# Basic_Arduino.net
KiCad netlist of a schematic drawn in EAGLE
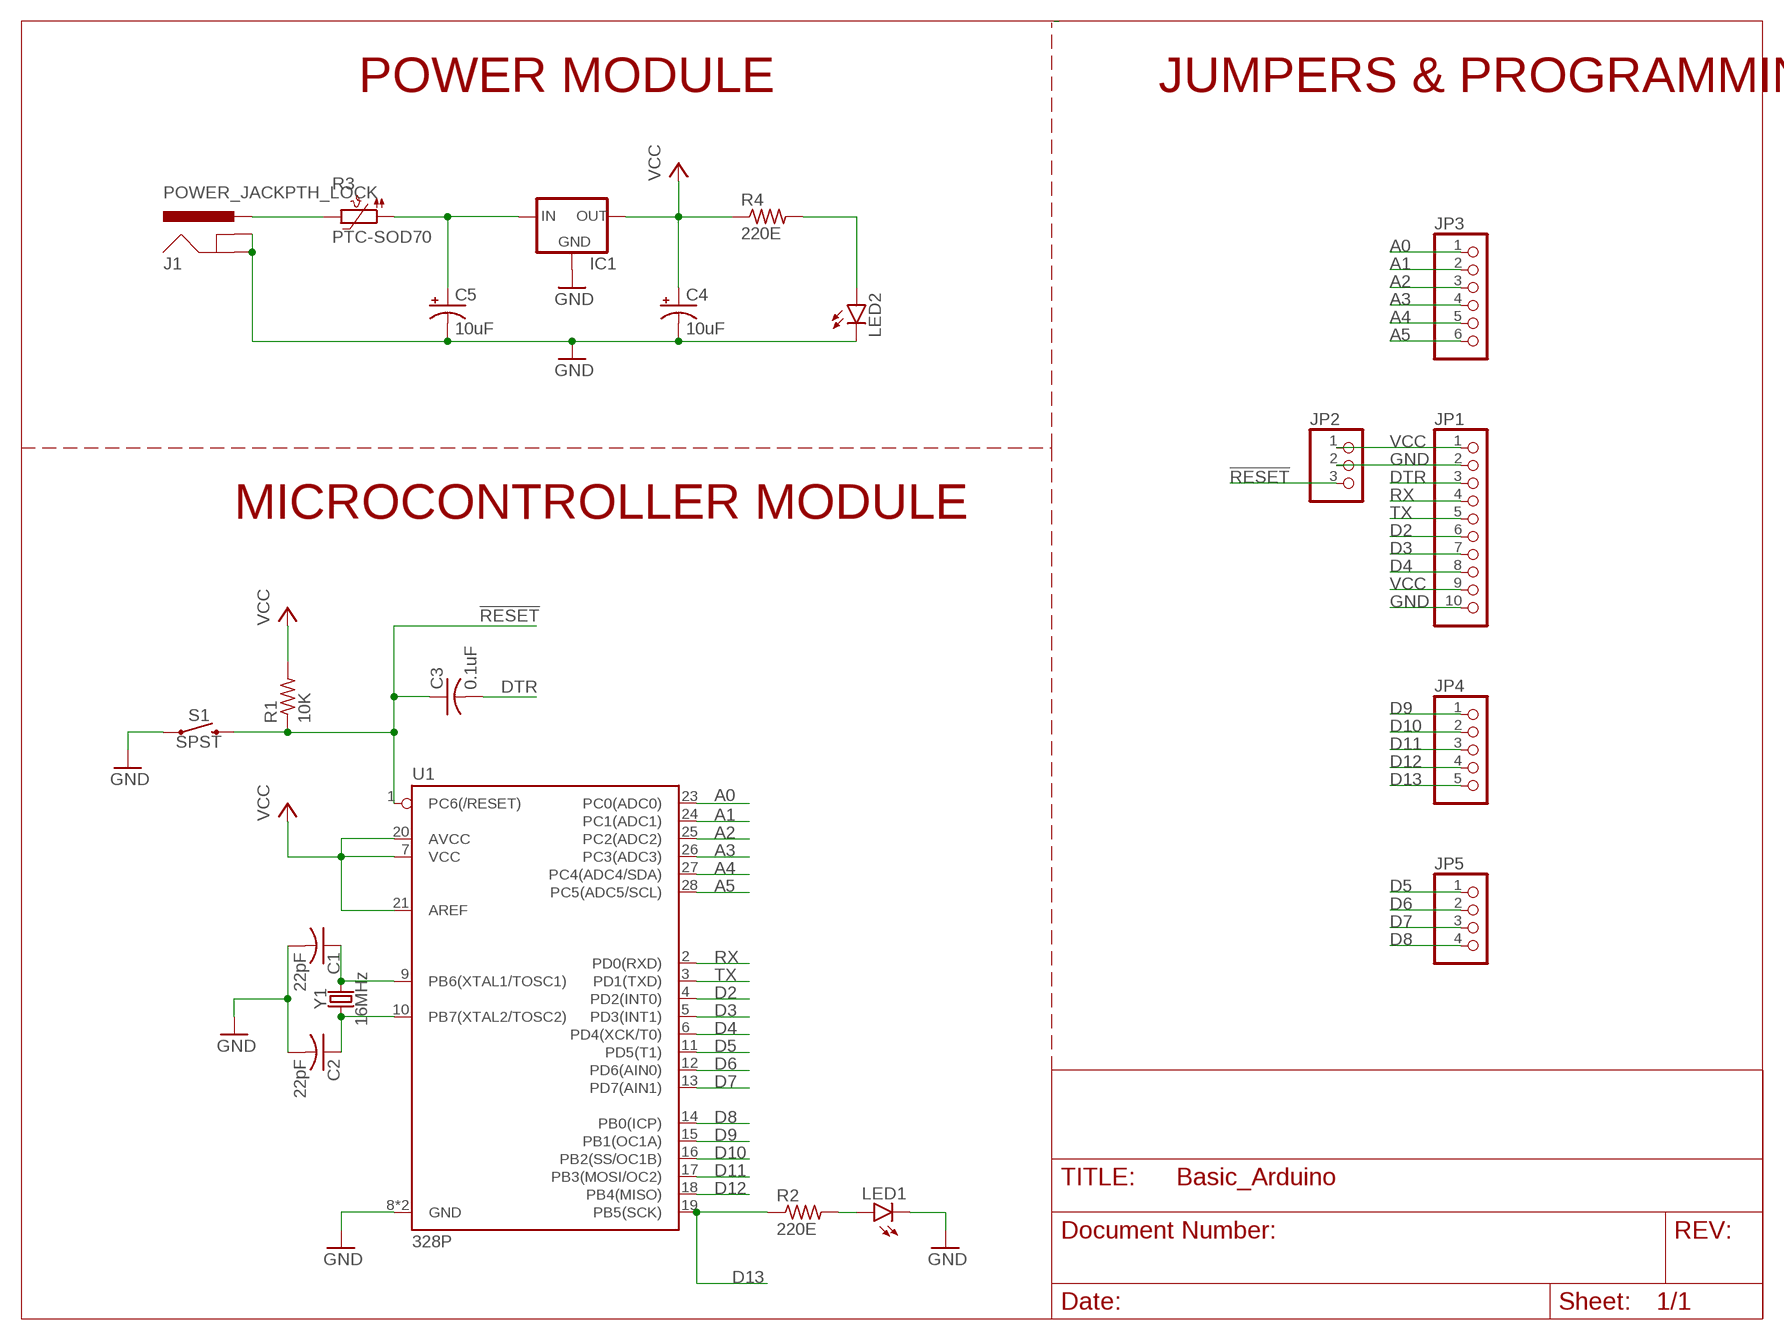
[diagram p0: schematic, sheet 1]

(export (version "E")
  (design (tool "Eeschema 10.0.6"))
  (components
    (comp (ref "C1")
      (value "22pF")
      (footprint "eagle-import:C025-024X044")
      (libsource (lib "eagle-import") (part "C-US025-024X044"))
    )
    (comp (ref "C2")
      (value "22pF")
      (footprint "eagle-import:C025-024X044")
      (libsource (lib "eagle-import") (part "C-US025-024X044"))
    )
    (comp (ref "C3")
      (value "0.1uF")
      (footprint "eagle-import:C025-024X044")
      (libsource (lib "eagle-import") (part "C-US025-024X044"))
    )
    (comp (ref "C4")
      (value "10uF")
      (footprint "eagle-import:E2,5-6E")
      (libsource (lib "eagle-import") (part "CPOL-USE2,5-6E"))
    )
    (comp (ref "C5")
      (value "10uF")
      (footprint "eagle-import:E2,5-6E")
      (libsource (lib "eagle-import") (part "CPOL-USE2,5-6E"))
    )
    (comp (ref "IC1")
      (value "78XXS")
      (footprint "eagle-import:78XXS")
      (libsource (lib "eagle-import") (part "78XXS"))
    )
    (comp (ref "J1")
      (value "POWER_JACKPTH_LOCK")
      (footprint "eagle-import:POWER_JACK_PTH_LOCK")
      (libsource (lib "eagle-import") (part "POWER_JACKPTH_LOCK"))
    )
    (comp (ref "JP1")
      (value "PINHD-1X10")
      (footprint "eagle-import:1X10")
      (libsource (lib "eagle-import") (part "PINHD-1X10"))
    )
    (comp (ref "JP2")
      (value "PINHD-1X3")
      (footprint "eagle-import:1X03")
      (libsource (lib "eagle-import") (part "PINHD-1X3"))
    )
    (comp (ref "JP3")
      (value "PINHD-1X6")
      (footprint "eagle-import:1X06")
      (libsource (lib "eagle-import") (part "PINHD-1X6"))
    )
    (comp (ref "JP4")
      (value "PINHD-1X5")
      (footprint "eagle-import:1X05")
      (libsource (lib "eagle-import") (part "PINHD-1X5"))
    )
    (comp (ref "JP5")
      (value "PINHD-1X4")
      (footprint "eagle-import:1X04")
      (libsource (lib "eagle-import") (part "PINHD-1X4"))
    )
    (comp (ref "LED1")
      (value "LED3MM")
      (footprint "eagle-import:LED3MM")
      (libsource (lib "eagle-import") (part "LED3MM"))
    )
    (comp (ref "LED2")
      (value "LED3MM")
      (footprint "eagle-import:LED3MM")
      (libsource (lib "eagle-import") (part "LED3MM"))
    )
    (comp (ref "R1")
      (value "10K")
      (footprint "eagle-import:0204_7")
      (libsource (lib "eagle-import") (part "R-US_0204/7"))
    )
    (comp (ref "R2")
      (value "220E")
      (footprint "eagle-import:0204_7")
      (libsource (lib "eagle-import") (part "R-US_0204/7"))
    )
    (comp (ref "R3")
      (value "PTC-SOD70")
      (footprint "eagle-import:SOD70")
      (libsource (lib "eagle-import") (part "PTC-SOD70"))
    )
    (comp (ref "R4")
      (value "220E")
      (footprint "eagle-import:0204_7")
      (libsource (lib "eagle-import") (part "R-US_0204/7"))
    )
    (comp (ref "S1")
      (value "SPST")
      (footprint "eagle-import:TACTILE_SWITCH_PTH_6.0MM")
      (libsource (lib "eagle-import") (part "MOMENTARY-SWITCH-SPST-PTH-6.0MM"))
    )
    (comp (ref "U1")
      (value "328P")
      (footprint "eagle-import:DIP28")
      (libsource (lib "eagle-import") (part "ATMEGA328P_PDIP"))
    )
    (comp (ref "Y1")
      (value "16MHz")
      (footprint "eagle-import:HC49US")
      (libsource (lib "eagle-import") (part "CRYSTAL-16MHZPTH-HC49US"))
    )
  )
  (nets
    (net (code "1") (name "/A0") (class "Default")
      (node (ref "JP3") (pin "1") (pinfunction "1_1") (pintype "passive"))
      (node (ref "U1") (pin "23") (pinfunction "PC0(ADC0)_23") (pintype "bidirectional"))
    )
    (net (code "2") (name "/A1") (class "Default")
      (node (ref "JP3") (pin "2") (pinfunction "2_2") (pintype "passive"))
      (node (ref "U1") (pin "24") (pinfunction "PC1(ADC1)_24") (pintype "bidirectional"))
    )
    (net (code "3") (name "/A2") (class "Default")
      (node (ref "JP3") (pin "3") (pinfunction "3_3") (pintype "passive"))
      (node (ref "U1") (pin "25") (pinfunction "PC2(ADC2)_25") (pintype "bidirectional"))
    )
    (net (code "4") (name "/A3") (class "Default")
      (node (ref "JP3") (pin "4") (pinfunction "4_4") (pintype "passive"))
      (node (ref "U1") (pin "26") (pinfunction "PC3(ADC3)_26") (pintype "bidirectional"))
    )
    (net (code "5") (name "/A4") (class "Default")
      (node (ref "JP3") (pin "5") (pinfunction "5_5") (pintype "passive"))
      (node (ref "U1") (pin "27") (pinfunction "PC4(ADC4/SDA)_27") (pintype "bidirectional"))
    )
    (net (code "6") (name "/A5") (class "Default")
      (node (ref "JP3") (pin "6") (pinfunction "6_6") (pintype "passive"))
      (node (ref "U1") (pin "28") (pinfunction "PC5(ADC5/SCL)_28") (pintype "bidirectional"))
    )
    (net (code "7") (name "/D2") (class "Default")
      (node (ref "JP1") (pin "6") (pinfunction "6_6") (pintype "passive"))
      (node (ref "U1") (pin "4") (pinfunction "PD2(INT0)_4") (pintype "bidirectional"))
    )
    (net (code "8") (name "/D3") (class "Default")
      (node (ref "JP1") (pin "7") (pinfunction "7_7") (pintype "passive"))
      (node (ref "U1") (pin "5") (pinfunction "PD3(INT1)_5") (pintype "bidirectional"))
    )
    (net (code "9") (name "/D4") (class "Default")
      (node (ref "JP1") (pin "8") (pinfunction "8_8") (pintype "passive"))
      (node (ref "U1") (pin "6") (pinfunction "PD4(XCK/T0)_6") (pintype "bidirectional"))
    )
    (net (code "10") (name "/D5") (class "Default")
      (node (ref "JP5") (pin "1") (pinfunction "1_1") (pintype "passive"))
      (node (ref "U1") (pin "11") (pinfunction "PD5(T1)_11") (pintype "bidirectional"))
    )
    (net (code "11") (name "/D6") (class "Default")
      (node (ref "JP5") (pin "2") (pinfunction "2_2") (pintype "passive"))
      (node (ref "U1") (pin "12") (pinfunction "PD6(AIN0)_12") (pintype "bidirectional"))
    )
    (net (code "12") (name "/D7") (class "Default")
      (node (ref "JP5") (pin "3") (pinfunction "3_3") (pintype "passive"))
      (node (ref "U1") (pin "13") (pinfunction "PD7(AIN1)_13") (pintype "bidirectional"))
    )
    (net (code "13") (name "/D8") (class "Default")
      (node (ref "JP5") (pin "4") (pinfunction "4_4") (pintype "passive"))
      (node (ref "U1") (pin "14") (pinfunction "PB0(ICP)_14") (pintype "bidirectional"))
    )
    (net (code "14") (name "/D9") (class "Default")
      (node (ref "JP4") (pin "1") (pinfunction "1_1") (pintype "passive"))
      (node (ref "U1") (pin "15") (pinfunction "PB1(OC1A)_15") (pintype "bidirectional"))
    )
    (net (code "15") (name "/D10") (class "Default")
      (node (ref "JP4") (pin "2") (pinfunction "2_2") (pintype "passive"))
      (node (ref "U1") (pin "16") (pinfunction "PB2(SS/OC1B)_16") (pintype "bidirectional"))
    )
    (net (code "16") (name "/D11") (class "Default")
      (node (ref "JP4") (pin "3") (pinfunction "3_3") (pintype "passive"))
      (node (ref "U1") (pin "17") (pinfunction "PB3(MOSI/OC2)_17") (pintype "bidirectional"))
    )
    (net (code "17") (name "/D12") (class "Default")
      (node (ref "JP4") (pin "4") (pinfunction "4_4") (pintype "passive"))
      (node (ref "U1") (pin "18") (pinfunction "PB4(MISO)_18") (pintype "bidirectional"))
    )
    (net (code "18") (name "/D13") (class "Default")
      (node (ref "JP4") (pin "5") (pinfunction "5_5") (pintype "passive"))
      (node (ref "R2") (pin "1") (pinfunction "1_1") (pintype "passive"))
      (node (ref "U1") (pin "19") (pinfunction "PB5(SCK)_19") (pintype "bidirectional"))
    )
    (net (code "19") (name "/DTR") (class "Default")
      (node (ref "C3") (pin "2") (pinfunction "2_2") (pintype "passive"))
      (node (ref "JP1") (pin "3") (pinfunction "3_3") (pintype "passive"))
    )
    (net (code "20") (name "/RX") (class "Default")
      (node (ref "JP1") (pin "4") (pinfunction "4_4") (pintype "passive"))
      (node (ref "U1") (pin "2") (pinfunction "PD0(RXD)_2") (pintype "bidirectional"))
    )
    (net (code "21") (name "/TX") (class "Default")
      (node (ref "JP1") (pin "5") (pinfunction "5_5") (pintype "passive"))
      (node (ref "U1") (pin "3") (pinfunction "PD1(TXD)_3") (pintype "bidirectional"))
    )
    (net (code "22") (name "/~{RESET}") (class "Default")
      (node (ref "C3") (pin "1") (pinfunction "1_1") (pintype "passive"))
      (node (ref "JP2") (pin "3") (pinfunction "3_3") (pintype "passive"))
      (node (ref "R1") (pin "1") (pinfunction "1_1") (pintype "passive"))
      (node (ref "S1") (pin "3") (pinfunction "2_3") (pintype "passive"))
      (node (ref "U1") (pin "1") (pinfunction "PC6(/RESET)_1") (pintype "bidirectional"))
    )
    (net (code "23") (name "GND") (class "Default")
      (node (ref "C1") (pin "2") (pinfunction "2_2") (pintype "passive"))
      (node (ref "C2") (pin "2") (pinfunction "2_2") (pintype "passive"))
      (node (ref "C4") (pin "-") (pinfunction "-_-") (pintype "passive"))
      (node (ref "C5") (pin "-") (pinfunction "-_-") (pintype "passive"))
      (node (ref "IC1") (pin "GND") (pinfunction "GND_GND") (pintype "input"))
      (node (ref "J1") (pin "GND") (pinfunction "GND_GND") (pintype "bidirectional"))
      (node (ref "J1") (pin "GNDBREAK") (pinfunction "GNDBREAK_GNDBREAK") (pintype "bidirectional"))
      (node (ref "JP1") (pin "10") (pinfunction "10_10") (pintype "passive"))
      (node (ref "JP1") (pin "2") (pinfunction "2_2") (pintype "passive"))
      (node (ref "JP2") (pin "2") (pinfunction "2_2") (pintype "passive"))
      (node (ref "LED1") (pin "K") (pinfunction "C_K") (pintype "passive"))
      (node (ref "LED2") (pin "K") (pinfunction "C_K") (pintype "passive"))
      (node (ref "S1") (pin "1") (pinfunction "1_1") (pintype "passive"))
      (node (ref "U1") (pin "22") (pinfunction "GND_22") (pintype "bidirectional"))
      (node (ref "U1") (pin "8") (pinfunction "GND_8") (pintype "bidirectional"))
    )
    (net (code "24") (name "Net-(C5-Pad+)") (class "Default")
      (node (ref "C5") (pin "+") (pinfunction "+_+") (pintype "passive"))
      (node (ref "IC1") (pin "IN") (pinfunction "IN_IN") (pintype "input"))
      (node (ref "R3") (pin "1") (pinfunction "1_1") (pintype "passive"))
    )
    (net (code "25") (name "Net-(J1-PadPWR)") (class "Default")
      (node (ref "J1") (pin "PWR") (pinfunction "PWR_PWR") (pintype "bidirectional"))
      (node (ref "R3") (pin "2") (pinfunction "2_2") (pintype "passive"))
    )
    (net (code "26") (name "Net-(LED1-PadA)") (class "Default")
      (node (ref "LED1") (pin "A") (pinfunction "A_A") (pintype "passive"))
      (node (ref "R2") (pin "2") (pinfunction "2_2") (pintype "passive"))
    )
    (net (code "27") (name "Net-(LED2-PadA)") (class "Default")
      (node (ref "LED2") (pin "A") (pinfunction "A_A") (pintype "passive"))
      (node (ref "R4") (pin "2") (pinfunction "2_2") (pintype "passive"))
    )
    (net (code "28") (name "Net-(U1-PB6(XTAL1{slash}TOSC1))") (class "Default")
      (node (ref "C1") (pin "1") (pinfunction "1_1") (pintype "passive"))
      (node (ref "U1") (pin "9") (pinfunction "PB6(XTAL1/TOSC1)_9") (pintype "bidirectional"))
      (node (ref "Y1") (pin "2") (pinfunction "2_2") (pintype "passive"))
    )
    (net (code "29") (name "Net-(U1-PB7(XTAL2{slash}TOSC2))") (class "Default")
      (node (ref "C2") (pin "1") (pinfunction "1_1") (pintype "passive"))
      (node (ref "U1") (pin "10") (pinfunction "PB7(XTAL2/TOSC2)_10") (pintype "bidirectional"))
      (node (ref "Y1") (pin "1") (pinfunction "1_1") (pintype "passive"))
    )
    (net (code "30") (name "VCC") (class "Default")
      (node (ref "C4") (pin "+") (pinfunction "+_+") (pintype "passive"))
      (node (ref "IC1") (pin "OUT") (pinfunction "OUT_OUT") (pintype "passive"))
      (node (ref "JP1") (pin "1") (pinfunction "1_1") (pintype "passive"))
      (node (ref "JP1") (pin "9") (pinfunction "9_9") (pintype "passive"))
      (node (ref "JP2") (pin "1") (pinfunction "1_1") (pintype "passive"))
      (node (ref "R1") (pin "2") (pinfunction "2_2") (pintype "passive"))
      (node (ref "R4") (pin "1") (pinfunction "1_1") (pintype "passive"))
      (node (ref "U1") (pin "20") (pinfunction "AVCC_20") (pintype "bidirectional"))
      (node (ref "U1") (pin "21") (pinfunction "AREF_21") (pintype "bidirectional"))
      (node (ref "U1") (pin "7") (pinfunction "VCC_7") (pintype "bidirectional"))
    )
  )
)
